# 02_5V_Regulator_Circuit.net
KiCad netlist of a schematic drawn in Altium Designer
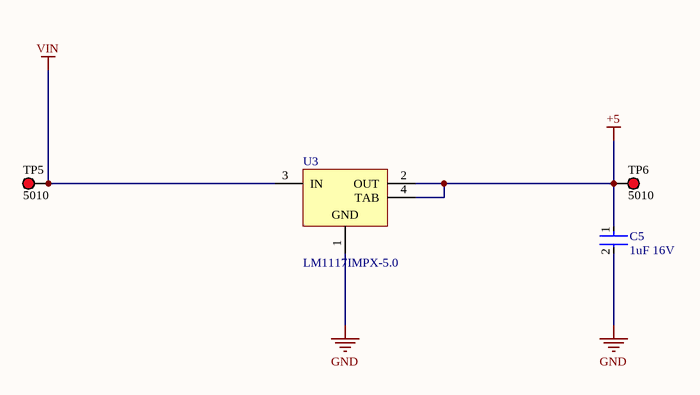
[diagram p0: 02_5V_Regulator_Circuit.SchDoc]

(export (version "E")
  (design (tool "Eeschema 10.0.6"))
  (components
    (comp (ref "C5")
      (value "1uF 16V")
      (footprint "FP-CL10B105KO8NNNC-MFG")
      (description "CAP CER 1UF 16V X7R 0603")
      (fields
        (field (name "OCTOPART") "https://octopart.com/cl10b105ko8nnnc-samsung-19018973")
        (field (name "MANUFACTURER") "Samsung Electro-Mechanics America, Inc")
      )
      (libsource (lib "Altium Content Vault") (part "b4654b650e69147ec39a6b967a45e02"))
    )
    (comp (ref "TP5")
      (value "5010")
      (footprint "KSTN-5010_V")
      (description "Test Point, Red, Through Hole, RoHS, Bulk")
      (fields (field (name "MANUFACTURER") "Keystone"))
      (libsource (lib "Altium Content Vault") (part "TESTPOINT_RED"))
    )
    (comp (ref "TP6")
      (value "5010")
      (footprint "KSTN-5010_V")
      (description "Test Point, Red, Through Hole, RoHS, Bulk")
      (fields (field (name "MANUFACTURER") "Keystone"))
      (libsource (lib "Altium Content Vault") (part "TESTPOINT_RED"))
    )
    (comp (ref "U3")
      (value "LM1117IMPX-5.0")
      (footprint "DCY0004A_M")
      (description "800mA Low-Dropout Linear Regulator, 4-pin SOT-223")
      (fields (field (name "MANUFACTURER") "Texas Instruments"))
      (libsource (lib "Altium Content Vault") (part "PM-REG-LM1086-SOT4"))
    )
  )
  (nets
    (net (code "1") (name "+5") (class "Default")
      (node (ref "C5") (pin "1") (pinfunction "1_1") (pintype "passive"))
      (node (ref "TP6") (pin "1") (pinfunction "1_1") (pintype "passive"))
      (node (ref "U3") (pin "2") (pinfunction "OUT_2") (pintype "power_in"))
      (node (ref "U3") (pin "4") (pinfunction "TAB_4") (pintype "power_in"))
    )
    (net (code "2") (name "GND") (class "Default")
      (node (ref "C5") (pin "2") (pinfunction "2_2") (pintype "passive"))
      (node (ref "U3") (pin "1") (pinfunction "GND_1") (pintype "power_in"))
    )
    (net (code "3") (name "VIN") (class "Default")
      (node (ref "TP5") (pin "1") (pinfunction "1_1") (pintype "passive"))
      (node (ref "U3") (pin "3") (pinfunction "IN_3") (pintype "power_in"))
    )
  )
)
